# satellite_interface.net
KiCad netlist of a schematic drawn in EAGLE
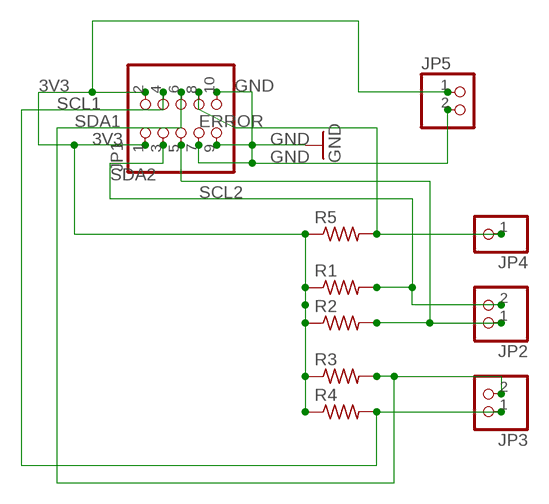
[diagram p0: schematic, sheet 1]

(export (version "E")
  (design (tool "Eeschema 10.0.6"))
  (components
    (comp (ref "JP1")
      (value "PINHD-2X5")
      (footprint "eagle-import:2X05")
      (libsource (lib "eagle-import") (part "PINHD-2X5"))
    )
    (comp (ref "JP2")
      (value "PINHD-1X2")
      (footprint "eagle-import:1X02")
      (libsource (lib "eagle-import") (part "PINHD-1X2"))
    )
    (comp (ref "JP3")
      (value "PINHD-1X2")
      (footprint "eagle-import:1X02")
      (libsource (lib "eagle-import") (part "PINHD-1X2"))
    )
    (comp (ref "JP4")
      (value "PINHD-1X1")
      (footprint "eagle-import:1X01")
      (libsource (lib "eagle-import") (part "PINHD-1X1"))
    )
    (comp (ref "JP5")
      (value "PINHD-1X2")
      (footprint "eagle-import:1X02")
      (libsource (lib "eagle-import") (part "PINHD-1X2"))
    )
    (comp (ref "R1")
      (value "R-US_M0805")
      (footprint "eagle-import:M0805")
      (libsource (lib "eagle-import") (part "R-US_M0805"))
    )
    (comp (ref "R2")
      (value "R-US_M0805")
      (footprint "eagle-import:M0805")
      (libsource (lib "eagle-import") (part "R-US_M0805"))
    )
    (comp (ref "R3")
      (value "R-US_M0805")
      (footprint "eagle-import:M0805")
      (libsource (lib "eagle-import") (part "R-US_M0805"))
    )
    (comp (ref "R4")
      (value "R-US_M0805")
      (footprint "eagle-import:M0805")
      (libsource (lib "eagle-import") (part "R-US_M0805"))
    )
    (comp (ref "R5")
      (value "R-US_M0805")
      (footprint "eagle-import:M0805")
      (libsource (lib "eagle-import") (part "R-US_M0805"))
    )
  )
  (nets
    (net (code "1") (name "/3V3") (class "Default")
      (node (ref "JP1") (pin "1") (pinfunction "1_1") (pintype "passive"))
      (node (ref "JP1") (pin "2") (pinfunction "2_2") (pintype "passive"))
      (node (ref "JP5") (pin "1") (pinfunction "1_1") (pintype "passive"))
      (node (ref "R1") (pin "1") (pinfunction "1_1") (pintype "passive"))
      (node (ref "R2") (pin "1") (pinfunction "1_1") (pintype "passive"))
      (node (ref "R3") (pin "1") (pinfunction "1_1") (pintype "passive"))
      (node (ref "R4") (pin "1") (pinfunction "1_1") (pintype "passive"))
      (node (ref "R5") (pin "1") (pinfunction "1_1") (pintype "passive"))
    )
    (net (code "2") (name "/ERROR") (class "Default")
      (node (ref "JP1") (pin "8") (pinfunction "8_8") (pintype "passive"))
      (node (ref "JP4") (pin "1") (pinfunction "1_1") (pintype "passive"))
      (node (ref "R5") (pin "2") (pinfunction "2_2") (pintype "passive"))
    )
    (net (code "3") (name "/SCL1") (class "Default")
      (node (ref "JP1") (pin "4") (pinfunction "4_4") (pintype "passive"))
      (node (ref "JP3") (pin "1") (pinfunction "1_1") (pintype "passive"))
      (node (ref "R4") (pin "2") (pinfunction "2_2") (pintype "passive"))
    )
    (net (code "4") (name "/SCL2") (class "Default")
      (node (ref "JP1") (pin "5") (pinfunction "5_5") (pintype "passive"))
      (node (ref "JP2") (pin "1") (pinfunction "1_1") (pintype "passive"))
      (node (ref "R2") (pin "2") (pinfunction "2_2") (pintype "passive"))
    )
    (net (code "5") (name "/SDA1") (class "Default")
      (node (ref "JP1") (pin "6") (pinfunction "6_6") (pintype "passive"))
      (node (ref "JP3") (pin "2") (pinfunction "2_2") (pintype "passive"))
      (node (ref "R3") (pin "2") (pinfunction "2_2") (pintype "passive"))
    )
    (net (code "6") (name "/SDA2") (class "Default")
      (node (ref "JP1") (pin "3") (pinfunction "3_3") (pintype "passive"))
      (node (ref "JP2") (pin "2") (pinfunction "2_2") (pintype "passive"))
      (node (ref "R1") (pin "2") (pinfunction "2_2") (pintype "passive"))
    )
    (net (code "7") (name "GND") (class "Default")
      (node (ref "JP1") (pin "10") (pinfunction "10_10") (pintype "passive"))
      (node (ref "JP1") (pin "7") (pinfunction "7_7") (pintype "passive"))
      (node (ref "JP1") (pin "9") (pinfunction "9_9") (pintype "passive"))
      (node (ref "JP5") (pin "2") (pinfunction "2_2") (pintype "passive"))
    )
  )
)
